# AccessControl.net
KiCad netlist of a schematic drawn in EAGLE
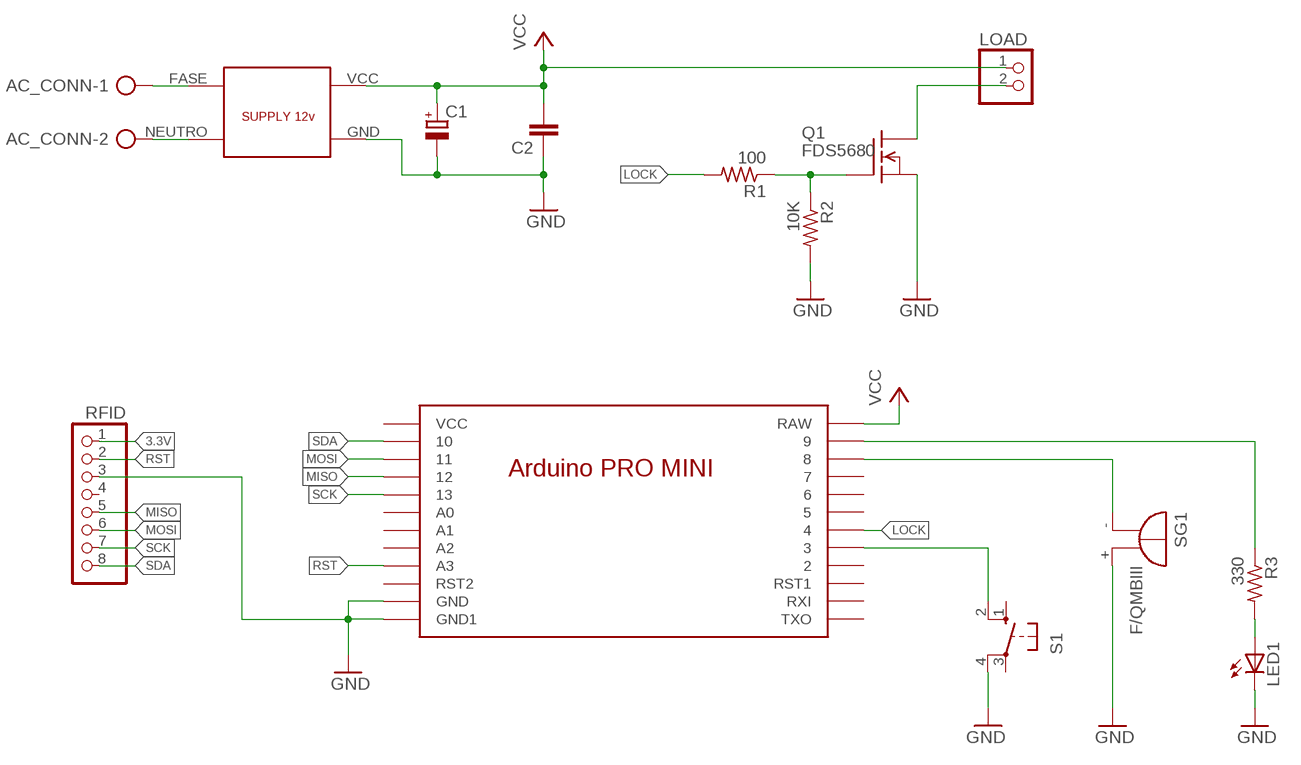
[diagram p0: schematic, sheet 1]

(export (version "E")
  (design (tool "Eeschema 10.0.6"))
  (components
    (comp (ref "AC_CONN")
      (value "AK300/2")
      (footprint "eagle-import:AK300_2")
      (libsource (lib "eagle-import") (part "AK300/2"))
    )
    (comp (ref "C1")
      (value "CPOL-EUE2.5-6")
      (footprint "eagle-import:E2,5-6")
      (libsource (lib "eagle-import") (part "CPOL-EUE2.5-6"))
    )
    (comp (ref "C2")
      (value "C2.5/2")
      (footprint "eagle-import:C2.5-2")
      (libsource (lib "eagle-import") (part "C2.5/2"))
    )
    (comp (ref "LED1")
      (value "LED3MM")
      (footprint "eagle-import:LED3MM")
      (libsource (lib "eagle-import") (part "LED3MM"))
    )
    (comp (ref "LOAD")
      (value "PINHD-1X2")
      (footprint "eagle-import:1X02")
      (libsource (lib "eagle-import") (part "PINHD-1X2"))
    )
    (comp (ref "Q1")
      (value "FDS5680")
      (footprint "eagle-import:SO-8")
      (libsource (lib "eagle-import") (part "FDS5680"))
    )
    (comp (ref "R1")
      (value "100")
      (footprint "eagle-import:0204_7")
      (libsource (lib "eagle-import") (part "R-US_0204/7"))
    )
    (comp (ref "R2")
      (value "10K")
      (footprint "eagle-import:0204_7")
      (libsource (lib "eagle-import") (part "R-US_0204/7"))
    )
    (comp (ref "R3")
      (value "330")
      (footprint "eagle-import:0204_7")
      (libsource (lib "eagle-import") (part "R-US_0204/7"))
    )
    (comp (ref "RFID")
      (value "PINHD-1X8")
      (footprint "eagle-import:1X08")
      (libsource (lib "eagle-import") (part "PINHD-1X8"))
    )
    (comp (ref "S1")
      (value "10-XX")
      (footprint "eagle-import:B3F-10XX")
      (fields (field (name "MPN") "B3F-1000"))
      (libsource (lib "eagle-import") (part "10-XX"))
    )
    (comp (ref "SG1")
      (value "F/QMBIII")
      (footprint "eagle-import:F_QMBIII")
      (libsource (lib "eagle-import") (part "F/QMBIII"))
    )
    (comp (ref "U$1")
      (value "NANO")
      (footprint "eagle-import:NANO")
      (libsource (lib "eagle-import") (part "NANO"))
    )
    (comp (ref "U$2")
      (value "SUPPLY12V")
      (footprint "eagle-import:SUPPLY12V")
      (libsource (lib "eagle-import") (part "SUPPLY12V"))
    )
  )
  (nets
    (net (code "1") (name "3.3V") (class "Default")
      (node (ref "RFID") (pin "1") (pinfunction "1_1") (pintype "passive"))
    )
    (net (code "2") (name "GND") (class "Default")
      (node (ref "C1") (pin "-") (pinfunction "-_-") (pintype "passive"))
      (node (ref "C2") (pin "1") (pinfunction "1_1") (pintype "passive"))
      (node (ref "LED1") (pin "K") (pinfunction "C_K") (pintype "passive"))
      (node (ref "Q1") (pin "1") (pinfunction "S_1") (pintype "passive"))
      (node (ref "Q1") (pin "2") (pinfunction "S_2") (pintype "passive"))
      (node (ref "Q1") (pin "3") (pinfunction "S_3") (pintype "passive"))
      (node (ref "R2") (pin "2") (pinfunction "2_2") (pintype "passive"))
      (node (ref "RFID") (pin "3") (pinfunction "3_3") (pintype "passive"))
      (node (ref "S1") (pin "4") (pinfunction "P1_4") (pintype "passive"))
      (node (ref "SG1") (pin "+") (pinfunction "-_+") (pintype "passive"))
      (node (ref "U$1") (pin "GND1") (pinfunction "GND_GND1") (pintype "bidirectional"))
      (node (ref "U$1") (pin "GND2") (pinfunction "GND1_GND2") (pintype "power_in"))
      (node (ref "U$2") (pin "GND") (pinfunction "GND_GND") (pintype "bidirectional"))
    )
    (net (code "3") (name "LOCK") (class "Default")
      (node (ref "R1") (pin "2") (pinfunction "2_2") (pintype "passive"))
      (node (ref "U$1") (pin "4") (pinfunction "4_4") (pintype "bidirectional"))
    )
    (net (code "4") (name "MISO") (class "Default")
      (node (ref "RFID") (pin "5") (pinfunction "5_5") (pintype "passive"))
      (node (ref "U$1") (pin "12") (pinfunction "12_12") (pintype "bidirectional"))
    )
    (net (code "5") (name "MOSI") (class "Default")
      (node (ref "RFID") (pin "6") (pinfunction "6_6") (pintype "passive"))
      (node (ref "U$1") (pin "11") (pinfunction "11_11") (pintype "bidirectional"))
    )
    (net (code "6") (name "Net-(AC_CONNA-KL)") (class "Default")
      (node (ref "AC_CONN") (pin "1") (pinfunction "KL_1") (pintype "passive"))
      (node (ref "U$2") (pin "FASE") (pinfunction "FASE_FASE") (pintype "bidirectional"))
    )
    (net (code "7") (name "Net-(AC_CONNB-KL)") (class "Default")
      (node (ref "AC_CONN") (pin "2") (pinfunction "KL_2") (pintype "passive"))
      (node (ref "U$2") (pin "NEUTRO") (pinfunction "NEUTRO_NEUTRO") (pintype "bidirectional"))
    )
    (net (code "8") (name "Net-(LED1-PadA)") (class "Default")
      (node (ref "LED1") (pin "A") (pinfunction "A_A") (pintype "passive"))
      (node (ref "R3") (pin "2") (pinfunction "2_2") (pintype "passive"))
    )
    (net (code "9") (name "Net-(LOAD-Pad2)") (class "Default")
      (node (ref "LOAD") (pin "2") (pinfunction "2_2") (pintype "passive"))
      (node (ref "Q1") (pin "5") (pinfunction "D_5") (pintype "passive"))
      (node (ref "Q1") (pin "6") (pinfunction "D_6") (pintype "passive"))
      (node (ref "Q1") (pin "7") (pinfunction "D_7") (pintype "passive"))
      (node (ref "Q1") (pin "8") (pinfunction "D_8") (pintype "passive"))
    )
    (net (code "10") (name "Net-(Q1-G)") (class "Default")
      (node (ref "Q1") (pin "4") (pinfunction "G_4") (pintype "passive"))
      (node (ref "R1") (pin "1") (pinfunction "1_1") (pintype "passive"))
      (node (ref "R2") (pin "1") (pinfunction "1_1") (pintype "passive"))
    )
    (net (code "11") (name "Net-(R3-Pad1)") (class "Default")
      (node (ref "R3") (pin "1") (pinfunction "1_1") (pintype "passive"))
      (node (ref "U$1") (pin "9") (pinfunction "9_9") (pintype "bidirectional"))
    )
    (net (code "12") (name "Net-(S1-S1)") (class "Default")
      (node (ref "S1") (pin "2") (pinfunction "S1_2") (pintype "passive"))
      (node (ref "U$1") (pin "3") (pinfunction "3_3") (pintype "bidirectional"))
    )
    (net (code "13") (name "Net-(SG1-+)") (class "Default")
      (node (ref "SG1") (pin "-") (pinfunction "+_-") (pintype "passive"))
      (node (ref "U$1") (pin "8") (pinfunction "8_8") (pintype "bidirectional"))
    )
    (net (code "14") (name "RST") (class "Default")
      (node (ref "RFID") (pin "2") (pinfunction "2_2") (pintype "passive"))
      (node (ref "U$1") (pin "A3") (pinfunction "A3_A3") (pintype "bidirectional"))
    )
    (net (code "15") (name "SCK") (class "Default")
      (node (ref "RFID") (pin "7") (pinfunction "7_7") (pintype "passive"))
      (node (ref "U$1") (pin "13") (pinfunction "13_13") (pintype "bidirectional"))
    )
    (net (code "16") (name "SDA") (class "Default")
      (node (ref "RFID") (pin "8") (pinfunction "8_8") (pintype "passive"))
      (node (ref "U$1") (pin "10") (pinfunction "10_10") (pintype "bidirectional"))
    )
    (net (code "17") (name "VCC") (class "Default")
      (node (ref "C1") (pin "+") (pinfunction "+_+") (pintype "passive"))
      (node (ref "C2") (pin "2") (pinfunction "2_2") (pintype "passive"))
      (node (ref "LOAD") (pin "1") (pinfunction "1_1") (pintype "passive"))
      (node (ref "U$1") (pin "RAW") (pinfunction "RAW_RAW") (pintype "bidirectional"))
      (node (ref "U$2") (pin "VCC") (pinfunction "VCC_VCC") (pintype "bidirectional"))
    )
    (net (code "18") (name "unconnected-(RFID-Pad4)") (class "Default")
      (node (ref "RFID") (pin "4") (pinfunction "4_4") (pintype "passive"))
    )
    (net (code "19") (name "unconnected-(S1-P-Pad3)") (class "Default")
      (node (ref "S1") (pin "3") (pinfunction "P_3") (pintype "passive"))
    )
    (net (code "20") (name "unconnected-(S1-S-Pad1)") (class "Default")
      (node (ref "S1") (pin "1") (pinfunction "S_1") (pintype "passive"))
    )
    (net (code "21") (name "unconnected-(U$1-Pad2)") (class "Default")
      (node (ref "U$1") (pin "2") (pinfunction "2_2") (pintype "bidirectional"))
    )
    (net (code "22") (name "unconnected-(U$1-Pad5)") (class "Default")
      (node (ref "U$1") (pin "5") (pinfunction "5_5") (pintype "bidirectional"))
    )
    (net (code "23") (name "unconnected-(U$1-Pad6)") (class "Default")
      (node (ref "U$1") (pin "6") (pinfunction "6_6") (pintype "bidirectional"))
    )
    (net (code "24") (name "unconnected-(U$1-Pad7)") (class "Default")
      (node (ref "U$1") (pin "7") (pinfunction "7_7") (pintype "bidirectional"))
    )
    (net (code "25") (name "unconnected-(U$1-PadA0)") (class "Default")
      (node (ref "U$1") (pin "A0") (pinfunction "A0_A0") (pintype "bidirectional"))
    )
    (net (code "26") (name "unconnected-(U$1-PadA1)") (class "Default")
      (node (ref "U$1") (pin "A1") (pinfunction "A1_A1") (pintype "bidirectional"))
    )
    (net (code "27") (name "unconnected-(U$1-PadA2)") (class "Default")
      (node (ref "U$1") (pin "A2") (pinfunction "A2_A2") (pintype "bidirectional"))
    )
    (net (code "28") (name "unconnected-(U$1-PadRST1)") (class "Default")
      (node (ref "U$1") (pin "RST1") (pinfunction "RST1_RST1") (pintype "bidirectional"))
    )
    (net (code "29") (name "unconnected-(U$1-PadRST2)") (class "Default")
      (node (ref "U$1") (pin "RST2") (pinfunction "RST2_RST2") (pintype "bidirectional"))
    )
    (net (code "30") (name "unconnected-(U$1-PadRXI)") (class "Default")
      (node (ref "U$1") (pin "RXI") (pinfunction "RXI_RXI") (pintype "bidirectional"))
    )
    (net (code "31") (name "unconnected-(U$1-PadTXO)") (class "Default")
      (node (ref "U$1") (pin "TXO") (pinfunction "TXO_TXO") (pintype "bidirectional"))
    )
    (net (code "32") (name "unconnected-(U$1-PadVCC)") (class "Default")
      (node (ref "U$1") (pin "VCC") (pinfunction "VCC_VCC") (pintype "bidirectional"))
    )
  )
)
